# ETHERNET_PHY.net
KiCad netlist of a schematic drawn in Altium Designer
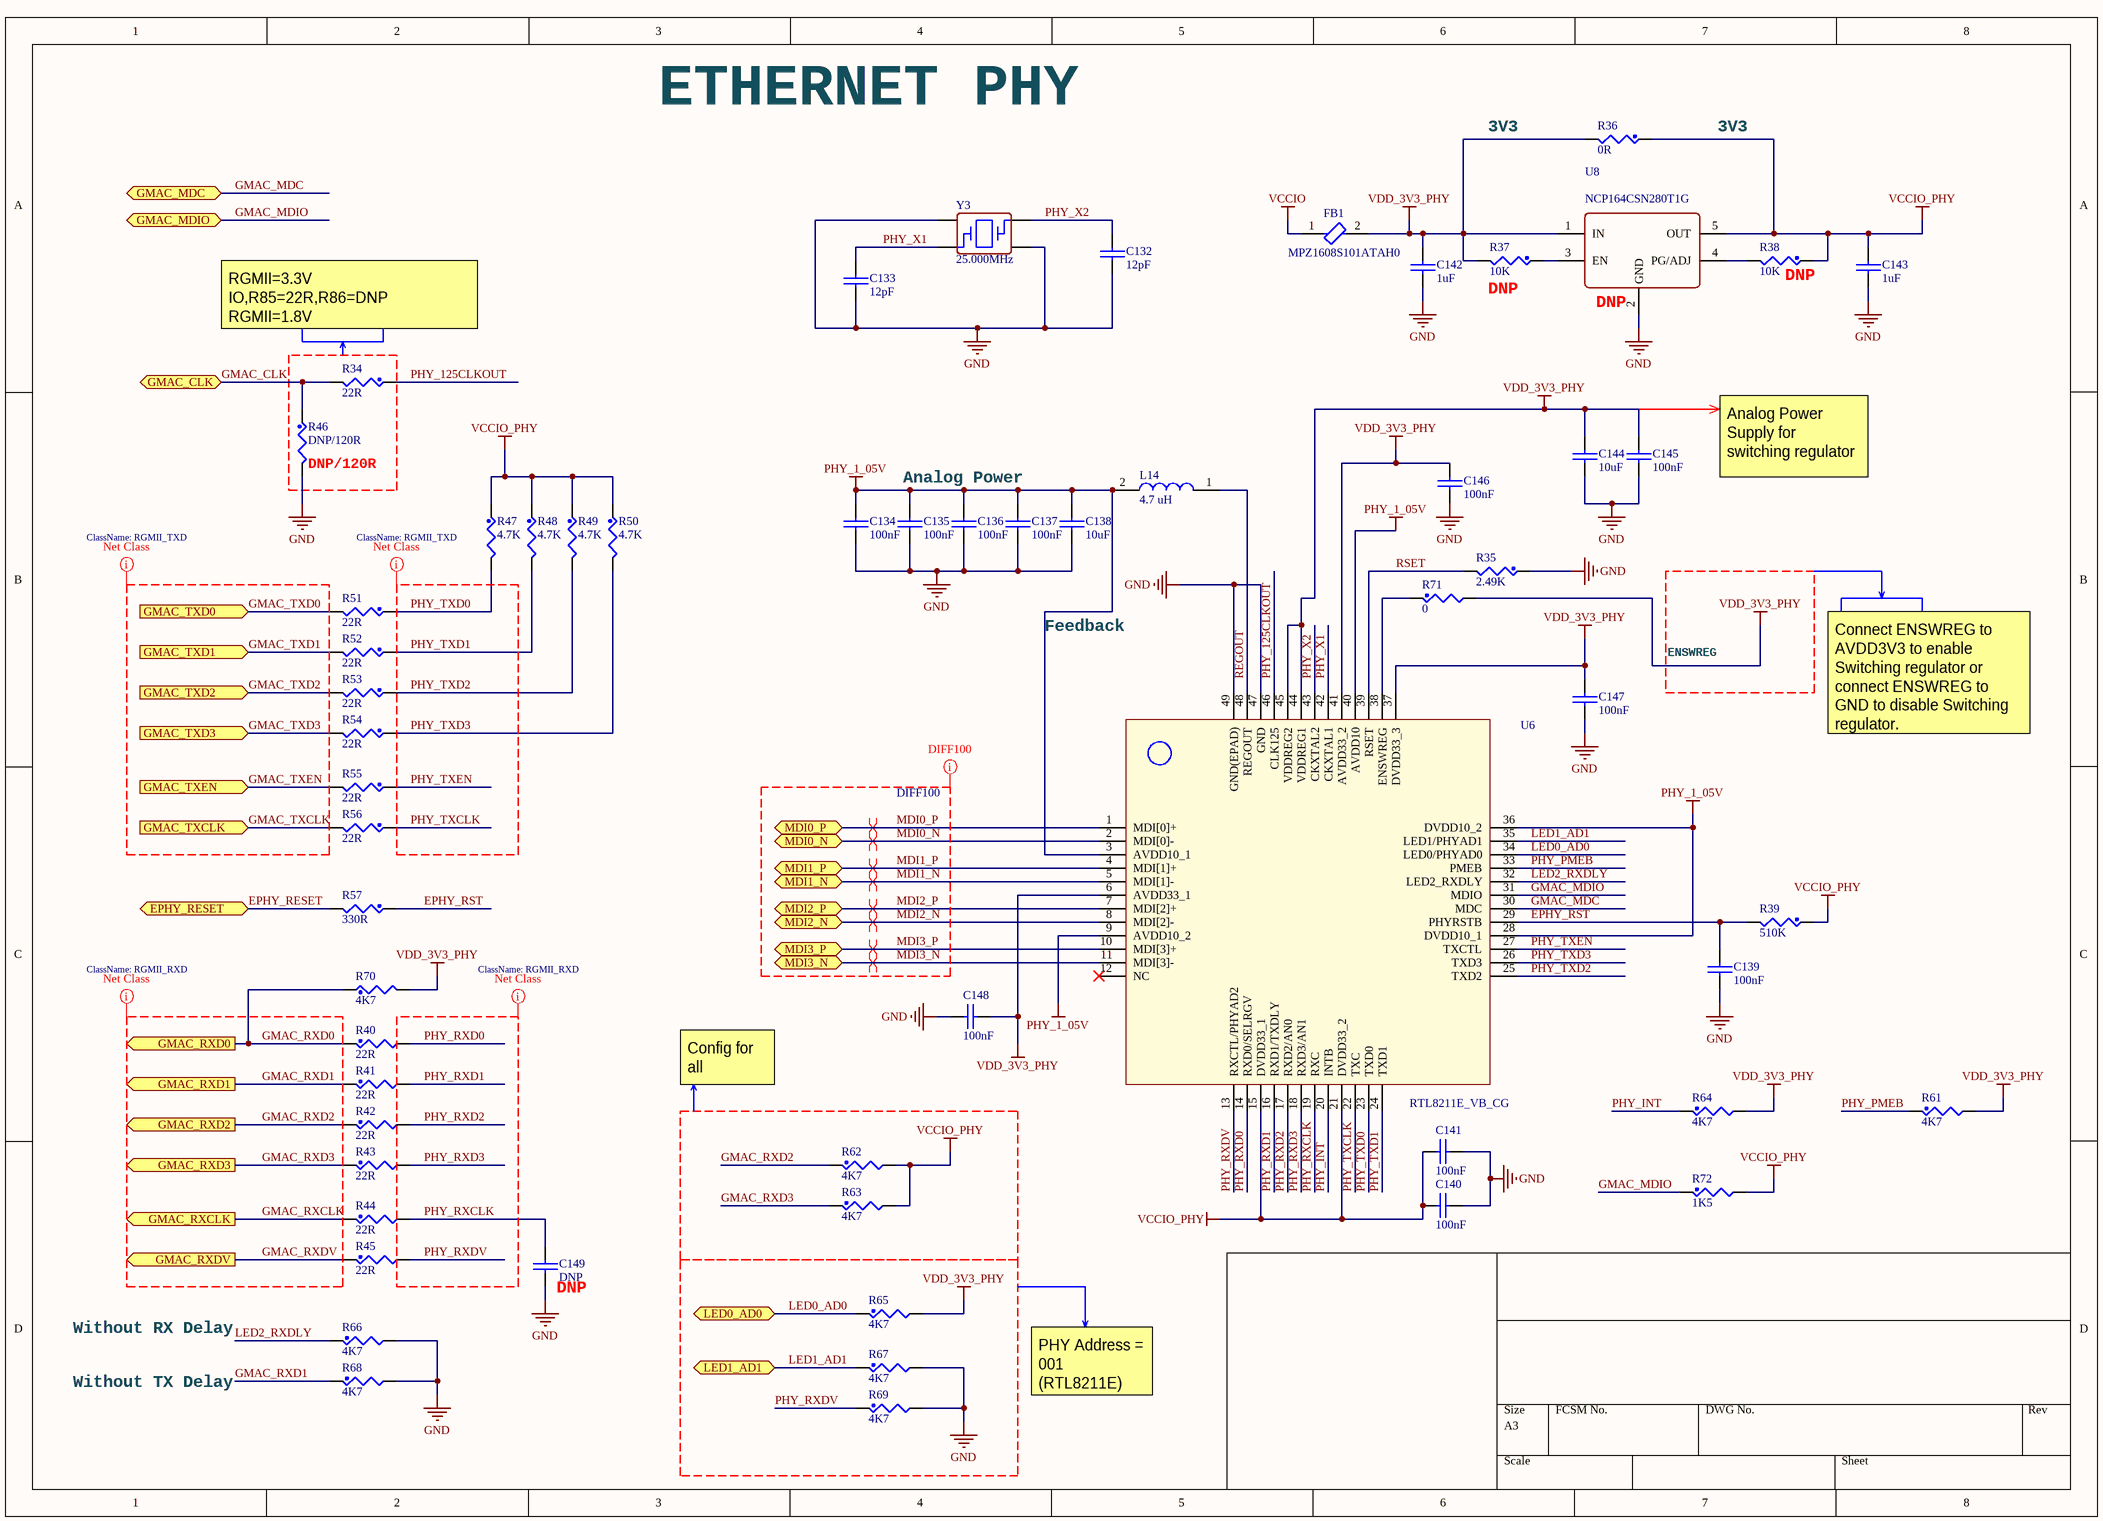
[diagram p0: ETHERNET_PHY.SchDoc]

(export (version "E")
  (design (tool "Eeschema 10.0.6"))
  (components
    (comp (ref "C132")
      (value "12pF")
      (footprint "0402_CC - C")
      (libsource (lib "AAR_RockChip_RK3328") (part "CAP_NP"))
    )
    (comp (ref "C133")
      (value "12pF")
      (footprint "0402_CC - C")
      (libsource (lib "AAR_RockChip_RK3328") (part "CAP_NP"))
    )
    (comp (ref "C134")
      (value "100nF")
      (footprint "0402_CC - C")
      (libsource (lib "AAR_RockChip_RK3328") (part "CAP_NP"))
    )
    (comp (ref "C135")
      (value "100nF")
      (footprint "0402_CC - C")
      (libsource (lib "AAR_RockChip_RK3328") (part "CAP_NP"))
    )
    (comp (ref "C136")
      (value "100nF")
      (footprint "0402_CC - C")
      (libsource (lib "AAR_RockChip_RK3328") (part "CAP_NP"))
    )
    (comp (ref "C137")
      (value "100nF")
      (footprint "0402_CC - C")
      (libsource (lib "AAR_RockChip_RK3328") (part "CAP_NP"))
    )
    (comp (ref "C138")
      (value "10uF")
      (footprint "0603_CC")
      (libsource (lib "AAR_RockChip_RK3328") (part "CAP_NP"))
    )
    (comp (ref "C139")
      (value "100nF")
      (footprint "0402_CC - C")
      (libsource (lib "AAR_RockChip_RK3328") (part "CAP_NP"))
    )
    (comp (ref "C140")
      (value "100nF")
      (footprint "0402_CC - C")
      (libsource (lib "AAR_RockChip_RK3328") (part "CAP_NP"))
    )
    (comp (ref "C141")
      (value "100nF")
      (footprint "0402_CC - C")
      (libsource (lib "AAR_RockChip_RK3328") (part "CAP_NP"))
    )
    (comp (ref "C142")
      (value "1uF")
      (footprint "0402_CC - C")
      (libsource (lib "AAR_RockChip_RK3328") (part "CAP_NP"))
    )
    (comp (ref "C143")
      (value "1uF")
      (footprint "0402_CC - C")
      (libsource (lib "AAR_RockChip_RK3328") (part "CAP_NP"))
    )
    (comp (ref "C144")
      (value "10uF")
      (footprint "0603_CC")
      (libsource (lib "AAR_RockChip_RK3328") (part "CAP_NP"))
    )
    (comp (ref "C145")
      (value "100nF")
      (footprint "0402_CC - C")
      (libsource (lib "AAR_RockChip_RK3328") (part "CAP_NP"))
    )
    (comp (ref "C146")
      (value "100nF")
      (footprint "0402_CC - C")
      (libsource (lib "AAR_RockChip_RK3328") (part "CAP_NP"))
    )
    (comp (ref "C147")
      (value "100nF")
      (footprint "0402_CC - C")
      (libsource (lib "AAR_RockChip_RK3328") (part "CAP_NP"))
    )
    (comp (ref "C148")
      (value "100nF")
      (footprint "0402_CC - C")
      (libsource (lib "AAR_RockChip_RK3328") (part "CAP_NP"))
    )
    (comp (ref "C149")
      (value "DNP")
      (footprint "0402_CC - C")
      (libsource (lib "AAR_RockChip_RK3328") (part "CAP_NP"))
    )
    (comp (ref "FB1")
      (value "MPZ1608S101ATAH0")
      (footprint "FP-MPZ1608-0_6-IPC_A")
      (description "Ferrite Beads 100ohms 3A 30mOhms 0603 Ferrite Chip\r\nCreator ARMAN")
      (fields (field (name "TOLERANCE") "25%") (field (name "MFR") "TDK"))
      (libsource (lib "AAR_RockChip_RK3328") (part "MPZ1608S101ATAH0"))
    )
    (comp (ref "L14")
      (value "4.7 uH")
      (footprint "1285ASH1R0MP2")
      (description "Fixed Inductors 08064.7 uH 20% 4.8A RDC=0.032ohms\r\nCreator Arman")
      (fields (field (name "MFR") "Murata Electronics") (field (name "MFR_PART_NO") "DFE201610E-4R7M=P2"))
      (libsource (lib "AAR_RockChip_RK3328") (part "DFE201610E_4R7M_P2_1"))
    )
    (comp (ref "R34")
      (value "22R")
      (footprint "0402_CR")
      (libsource (lib "AAR_RockChip_RK3328") (part "RES"))
    )
    (comp (ref "R35")
      (value "2.49K")
      (footprint "0402_CR")
      (libsource (lib "AAR_RockChip_RK3328") (part "RES"))
    )
    (comp (ref "R36") (value "0R") (footprint "0402_CR") (libsource (lib "AAR_RockChip_RK3328") (part "RES")))
    (comp (ref "R37")
      (value "10K")
      (footprint "0402_CR")
      (libsource (lib "AAR_RockChip_RK3328") (part "RES"))
    )
    (comp (ref "R38")
      (value "10K")
      (footprint "0402_CR")
      (libsource (lib "AAR_RockChip_RK3328") (part "RES"))
    )
    (comp (ref "R39")
      (value "510K")
      (footprint "0402_CR")
      (libsource (lib "AAR_RockChip_RK3328") (part "RES"))
    )
    (comp (ref "R40")
      (value "22R")
      (footprint "0402_CR")
      (libsource (lib "AAR_RockChip_RK3328") (part "RES"))
    )
    (comp (ref "R41")
      (value "22R")
      (footprint "0402_CR")
      (libsource (lib "AAR_RockChip_RK3328") (part "RES"))
    )
    (comp (ref "R42")
      (value "22R")
      (footprint "0402_CR")
      (libsource (lib "AAR_RockChip_RK3328") (part "RES"))
    )
    (comp (ref "R43")
      (value "22R")
      (footprint "0402_CR")
      (libsource (lib "AAR_RockChip_RK3328") (part "RES"))
    )
    (comp (ref "R44")
      (value "22R")
      (footprint "0402_CR")
      (libsource (lib "AAR_RockChip_RK3328") (part "RES"))
    )
    (comp (ref "R45")
      (value "22R")
      (footprint "0402_CR")
      (libsource (lib "AAR_RockChip_RK3328") (part "RES"))
    )
    (comp (ref "R46")
      (value "DNP/120R")
      (footprint "0402_CR")
      (libsource (lib "AAR_RockChip_RK3328") (part "RES"))
    )
    (comp (ref "R47")
      (value "4.7K")
      (footprint "0402_CR")
      (libsource (lib "AAR_RockChip_RK3328") (part "RES"))
    )
    (comp (ref "R48")
      (value "4.7K")
      (footprint "0402_CR")
      (libsource (lib "AAR_RockChip_RK3328") (part "RES"))
    )
    (comp (ref "R49")
      (value "4.7K")
      (footprint "0402_CR")
      (libsource (lib "AAR_RockChip_RK3328") (part "RES"))
    )
    (comp (ref "R50")
      (value "4.7K")
      (footprint "0402_CR")
      (libsource (lib "AAR_RockChip_RK3328") (part "RES"))
    )
    (comp (ref "R51")
      (value "22R")
      (footprint "0402_CR")
      (libsource (lib "AAR_RockChip_RK3328") (part "RES"))
    )
    (comp (ref "R52")
      (value "22R")
      (footprint "0402_CR")
      (libsource (lib "AAR_RockChip_RK3328") (part "RES"))
    )
    (comp (ref "R53")
      (value "22R")
      (footprint "0402_CR")
      (libsource (lib "AAR_RockChip_RK3328") (part "RES"))
    )
    (comp (ref "R54")
      (value "22R")
      (footprint "0402_CR")
      (libsource (lib "AAR_RockChip_RK3328") (part "RES"))
    )
    (comp (ref "R55")
      (value "22R")
      (footprint "0402_CR")
      (libsource (lib "AAR_RockChip_RK3328") (part "RES"))
    )
    (comp (ref "R56")
      (value "22R")
      (footprint "0402_CR")
      (libsource (lib "AAR_RockChip_RK3328") (part "RES"))
    )
    (comp (ref "R57")
      (value "330R")
      (footprint "0402_CR")
      (libsource (lib "AAR_RockChip_RK3328") (part "RES"))
    )
    (comp (ref "R61")
      (value "4K7")
      (footprint "0402_CR")
      (libsource (lib "AAR_RockChip_RK3328") (part "RES"))
    )
    (comp (ref "R62")
      (value "4K7")
      (footprint "0402_CR")
      (libsource (lib "AAR_RockChip_RK3328") (part "RES"))
    )
    (comp (ref "R63")
      (value "4K7")
      (footprint "0402_CR")
      (libsource (lib "AAR_RockChip_RK3328") (part "RES"))
    )
    (comp (ref "R64")
      (value "4K7")
      (footprint "0402_CR")
      (libsource (lib "AAR_RockChip_RK3328") (part "RES"))
    )
    (comp (ref "R65")
      (value "4K7")
      (footprint "0402_CR")
      (libsource (lib "AAR_RockChip_RK3328") (part "RES"))
    )
    (comp (ref "R66")
      (value "4K7")
      (footprint "0402_CR")
      (libsource (lib "AAR_RockChip_RK3328") (part "RES"))
    )
    (comp (ref "R67")
      (value "4K7")
      (footprint "0402_CR")
      (libsource (lib "AAR_RockChip_RK3328") (part "RES"))
    )
    (comp (ref "R68")
      (value "4K7")
      (footprint "0402_CR")
      (libsource (lib "AAR_RockChip_RK3328") (part "RES"))
    )
    (comp (ref "R69")
      (value "4K7")
      (footprint "0402_CR")
      (libsource (lib "AAR_RockChip_RK3328") (part "RES"))
    )
    (comp (ref "R70")
      (value "4K7")
      (footprint "0402_CR")
      (libsource (lib "AAR_RockChip_RK3328") (part "RES"))
    )
    (comp (ref "R71") (value "0") (footprint "0402_CR") (libsource (lib "AAR_RockChip_RK3328") (part "RES")))
    (comp (ref "R72")
      (value "1K5")
      (footprint "0402_CR")
      (libsource (lib "AAR_RockChip_RK3328") (part "RES"))
    )
    (comp (ref "U6")
      (value "RTL8211E_VB_CG")
      (footprint "QFN40P600X600X100-49N")
      (fields (field (name "MFR_PART_NO") "RTL8211E-VB-CG") (field (name "LCSC PART #") "C90735"))
      (libsource (lib "AAR_RockChip_RK3328") (part "RTL8211E_VB_CG"))
    )
    (comp (ref "U8")
      (value "NCP164CSN280T1G")
      (footprint "TSOP-5")
      (description "LDO Regulator, 300mA,\r\nLow Dropout Voltage, Ultra\r\nLow Noise, High PSRR with\r\nPower Good")
      (fields (field (name "MFR") "ON Semiconductor"))
      (libsource (lib "AAR_RockChip_RK3328") (part "NCP164CSN280T1G"))
    )
    (comp (ref "Y3")
      (value "25.000MHz")
      (footprint "ABM8G")
      (description "CRYSTAL 25MHZ 18PF SMD\r\nCreated by Arman Arvand")
      (fields
        (field (name "MFR") "Abracon Corporation")
        (field (name "MFR_PART_NO") "ABM8G-25.000MHZ-18-D2Y-T")
      )
      (libsource (lib "AAR_RockChip_RK3328") (part "ABM8G-25.000MHZ-18-D2Y-T"))
    )
  )
  (nets
    (net (code "1") (name "/EPHY_RESET") (class "Default")
      (node (ref "R57") (pin "2") (pinfunction "2_2") (pintype "passive"))
    )
    (net (code "2") (name "/EPHY_RST") (class "Default")
      (node (ref "C139") (pin "1") (pinfunction "1_1") (pintype "passive"))
      (node (ref "R39") (pin "2") (pinfunction "2_2") (pintype "passive"))
      (node (ref "R57") (pin "1") (pinfunction "1_1") (pintype "passive"))
      (node (ref "U6") (pin "29") (pinfunction "PHYRSTB_29") (pintype "passive"))
    )
    (net (code "3") (name "/GMAC_CLK") (class "Default")
      (node (ref "R34") (pin "2") (pinfunction "2_2") (pintype "passive"))
      (node (ref "R46") (pin "1") (pinfunction "1_1") (pintype "passive"))
    )
    (net (code "4") (name "/GMAC_MDC") (class "Default")
      (node (ref "U6") (pin "30") (pinfunction "MDC_30") (pintype "passive"))
    )
    (net (code "5") (name "/GMAC_MDIO") (class "Default")
      (node (ref "R72") (pin "1") (pinfunction "1_1") (pintype "passive"))
      (node (ref "U6") (pin "31") (pinfunction "MDIO_31") (pintype "passive"))
    )
    (net (code "6") (name "/GMAC_RXCLK") (class "Default")
      (node (ref "R44") (pin "1") (pinfunction "1_1") (pintype "passive"))
    )
    (net (code "7") (name "/GMAC_RXD0") (class "Default")
      (node (ref "R40") (pin "1") (pinfunction "1_1") (pintype "passive"))
      (node (ref "R70") (pin "1") (pinfunction "1_1") (pintype "passive"))
    )
    (net (code "8") (name "/GMAC_RXD1") (class "Default")
      (node (ref "R41") (pin "1") (pinfunction "1_1") (pintype "passive"))
      (node (ref "R68") (pin "1") (pinfunction "1_1") (pintype "passive"))
    )
    (net (code "9") (name "/GMAC_RXD2") (class "Default")
      (node (ref "R42") (pin "1") (pinfunction "1_1") (pintype "passive"))
      (node (ref "R62") (pin "1") (pinfunction "1_1") (pintype "passive"))
    )
    (net (code "10") (name "/GMAC_RXD3") (class "Default")
      (node (ref "R43") (pin "1") (pinfunction "1_1") (pintype "passive"))
      (node (ref "R63") (pin "1") (pinfunction "1_1") (pintype "passive"))
    )
    (net (code "11") (name "/GMAC_RXDV") (class "Default")
      (node (ref "R45") (pin "1") (pinfunction "1_1") (pintype "passive"))
    )
    (net (code "12") (name "/GMAC_TXCLK") (class "Default")
      (node (ref "R56") (pin "2") (pinfunction "2_2") (pintype "passive"))
    )
    (net (code "13") (name "/GMAC_TXD0") (class "Default")
      (node (ref "R51") (pin "2") (pinfunction "2_2") (pintype "passive"))
    )
    (net (code "14") (name "/GMAC_TXD1") (class "Default")
      (node (ref "R52") (pin "2") (pinfunction "2_2") (pintype "passive"))
    )
    (net (code "15") (name "/GMAC_TXD2") (class "Default")
      (node (ref "R53") (pin "2") (pinfunction "2_2") (pintype "passive"))
    )
    (net (code "16") (name "/GMAC_TXD3") (class "Default")
      (node (ref "R54") (pin "2") (pinfunction "2_2") (pintype "passive"))
    )
    (net (code "17") (name "/GMAC_TXEN") (class "Default")
      (node (ref "R55") (pin "2") (pinfunction "2_2") (pintype "passive"))
    )
    (net (code "18") (name "/LED0_AD0") (class "Default")
      (node (ref "R65") (pin "1") (pinfunction "1_1") (pintype "passive"))
      (node (ref "U6") (pin "34") (pinfunction "LED0/PHYAD0_34") (pintype "passive"))
    )
    (net (code "19") (name "/LED1_AD1") (class "Default")
      (node (ref "R67") (pin "1") (pinfunction "1_1") (pintype "passive"))
      (node (ref "U6") (pin "35") (pinfunction "LED1/PHYAD1_35") (pintype "passive"))
    )
    (net (code "20") (name "/LED2_RXDLY") (class "Default")
      (node (ref "R66") (pin "1") (pinfunction "1_1") (pintype "passive"))
      (node (ref "U6") (pin "32") (pinfunction "LED2_RXDLY_32") (pintype "passive"))
    )
    (net (code "21") (name "/MDI0_N") (class "Default")
      (node (ref "U6") (pin "2") (pinfunction "MDI[0]-_2") (pintype "passive"))
    )
    (net (code "22") (name "/MDI0_P") (class "Default")
      (node (ref "U6") (pin "1") (pinfunction "MDI[0]+_1") (pintype "passive"))
    )
    (net (code "23") (name "/MDI1_N") (class "Default")
      (node (ref "U6") (pin "5") (pinfunction "MDI[1]-_5") (pintype "passive"))
    )
    (net (code "24") (name "/MDI1_P") (class "Default")
      (node (ref "U6") (pin "4") (pinfunction "MDI[1]+_4") (pintype "passive"))
    )
    (net (code "25") (name "/MDI2_N") (class "Default")
      (node (ref "U6") (pin "8") (pinfunction "MDI[2]-_8") (pintype "passive"))
    )
    (net (code "26") (name "/MDI2_P") (class "Default")
      (node (ref "U6") (pin "7") (pinfunction "MDI[2]+_7") (pintype "passive"))
    )
    (net (code "27") (name "/MDI3_N") (class "Default")
      (node (ref "U6") (pin "11") (pinfunction "MDI[3]-_11") (pintype "passive"))
    )
    (net (code "28") (name "/MDI3_P") (class "Default")
      (node (ref "U6") (pin "10") (pinfunction "MDI[3]+_10") (pintype "passive"))
    )
    (net (code "29") (name "/PHY_125CLKOUT") (class "Default")
      (node (ref "R34") (pin "1") (pinfunction "1_1") (pintype "passive"))
      (node (ref "U6") (pin "46") (pinfunction "CLK125_46") (pintype "passive"))
    )
    (net (code "30") (name "/PHY_INT") (class "Default")
      (node (ref "R64") (pin "1") (pinfunction "1_1") (pintype "passive"))
      (node (ref "U6") (pin "20") (pinfunction "INTB_20") (pintype "passive"))
    )
    (net (code "31") (name "/PHY_PMEB") (class "Default")
      (node (ref "R61") (pin "1") (pinfunction "1_1") (pintype "passive"))
      (node (ref "U6") (pin "33") (pinfunction "PMEB_33") (pintype "passive"))
    )
    (net (code "32") (name "/PHY_RXCLK") (class "Default")
      (node (ref "C149") (pin "2") (pinfunction "2_2") (pintype "passive"))
      (node (ref "R44") (pin "2") (pinfunction "2_2") (pintype "passive"))
      (node (ref "U6") (pin "19") (pinfunction "RXC_19") (pintype "passive"))
    )
    (net (code "33") (name "/PHY_RXD0") (class "Default")
      (node (ref "R40") (pin "2") (pinfunction "2_2") (pintype "passive"))
      (node (ref "U6") (pin "14") (pinfunction "RXD0/SELRGV_14") (pintype "passive"))
    )
    (net (code "34") (name "/PHY_RXD1") (class "Default")
      (node (ref "R41") (pin "2") (pinfunction "2_2") (pintype "passive"))
      (node (ref "U6") (pin "16") (pinfunction "RXD1/TXDLY_16") (pintype "passive"))
    )
    (net (code "35") (name "/PHY_RXD2") (class "Default")
      (node (ref "R42") (pin "2") (pinfunction "2_2") (pintype "passive"))
      (node (ref "U6") (pin "17") (pinfunction "RXD2/AN0_17") (pintype "passive"))
    )
    (net (code "36") (name "/PHY_RXD3") (class "Default")
      (node (ref "R43") (pin "2") (pinfunction "2_2") (pintype "passive"))
      (node (ref "U6") (pin "18") (pinfunction "RXD3/AN1_18") (pintype "passive"))
    )
    (net (code "37") (name "/PHY_RXDV") (class "Default")
      (node (ref "R45") (pin "2") (pinfunction "2_2") (pintype "passive"))
      (node (ref "R69") (pin "1") (pinfunction "1_1") (pintype "passive"))
      (node (ref "U6") (pin "13") (pinfunction "RXCTL/PHYAD2_13") (pintype "passive"))
    )
    (net (code "38") (name "/PHY_TXCLK") (class "Default")
      (node (ref "R56") (pin "1") (pinfunction "1_1") (pintype "passive"))
      (node (ref "U6") (pin "22") (pinfunction "TXC_22") (pintype "passive"))
    )
    (net (code "39") (name "/PHY_TXD0") (class "Default")
      (node (ref "R47") (pin "2") (pinfunction "2_2") (pintype "passive"))
      (node (ref "R51") (pin "1") (pinfunction "1_1") (pintype "passive"))
      (node (ref "U6") (pin "23") (pinfunction "TXD0_23") (pintype "passive"))
    )
    (net (code "40") (name "/PHY_TXD1") (class "Default")
      (node (ref "R48") (pin "2") (pinfunction "2_2") (pintype "passive"))
      (node (ref "R52") (pin "1") (pinfunction "1_1") (pintype "passive"))
      (node (ref "U6") (pin "24") (pinfunction "TXD1_24") (pintype "passive"))
    )
    (net (code "41") (name "/PHY_TXD2") (class "Default")
      (node (ref "R49") (pin "2") (pinfunction "2_2") (pintype "passive"))
      (node (ref "R53") (pin "1") (pinfunction "1_1") (pintype "passive"))
      (node (ref "U6") (pin "25") (pinfunction "TXD2_25") (pintype "passive"))
    )
    (net (code "42") (name "/PHY_TXD3") (class "Default")
      (node (ref "R50") (pin "2") (pinfunction "2_2") (pintype "passive"))
      (node (ref "R54") (pin "1") (pinfunction "1_1") (pintype "passive"))
      (node (ref "U6") (pin "26") (pinfunction "TXD3_26") (pintype "passive"))
    )
    (net (code "43") (name "/PHY_TXEN") (class "Default")
      (node (ref "R55") (pin "1") (pinfunction "1_1") (pintype "passive"))
      (node (ref "U6") (pin "27") (pinfunction "TXCTL_27") (pintype "passive"))
    )
    (net (code "44") (name "/PHY_X1") (class "Default")
      (node (ref "C133") (pin "1") (pinfunction "1_1") (pintype "passive"))
      (node (ref "U6") (pin "42") (pinfunction "CKXTAL1_42") (pintype "passive"))
      (node (ref "Y3") (pin "1") (pinfunction "1_1") (pintype "passive"))
    )
    (net (code "45") (name "/PHY_X2") (class "Default")
      (node (ref "C132") (pin "1") (pinfunction "1_1") (pintype "passive"))
      (node (ref "U6") (pin "43") (pinfunction "CKXTAL2_43") (pintype "passive"))
      (node (ref "Y3") (pin "3") (pinfunction "3_3") (pintype "passive"))
    )
    (net (code "46") (name "/REGOUT") (class "Default")
      (node (ref "L14") (pin "1") (pinfunction "1_1") (pintype "passive"))
      (node (ref "U6") (pin "48") (pinfunction "REGOUT_48") (pintype "passive"))
    )
    (net (code "47") (name "/RSET") (class "Default")
      (node (ref "R35") (pin "2") (pinfunction "2_2") (pintype "passive"))
      (node (ref "U6") (pin "39") (pinfunction "RSET_39") (pintype "passive"))
    )
    (net (code "48") (name "GND") (class "Default")
      (node (ref "C132") (pin "2") (pinfunction "2_2") (pintype "passive"))
      (node (ref "C133") (pin "2") (pinfunction "2_2") (pintype "passive"))
      (node (ref "C134") (pin "2") (pinfunction "2_2") (pintype "passive"))
      (node (ref "C135") (pin "2") (pinfunction "2_2") (pintype "passive"))
      (node (ref "C136") (pin "2") (pinfunction "2_2") (pintype "passive"))
      (node (ref "C137") (pin "2") (pinfunction "2_2") (pintype "passive"))
      (node (ref "C138") (pin "2") (pinfunction "2_2") (pintype "passive"))
      (node (ref "C139") (pin "2") (pinfunction "2_2") (pintype "passive"))
      (node (ref "C140") (pin "2") (pinfunction "2_2") (pintype "passive"))
      (node (ref "C141") (pin "2") (pinfunction "2_2") (pintype "passive"))
      (node (ref "C142") (pin "2") (pinfunction "2_2") (pintype "passive"))
      (node (ref "C143") (pin "2") (pinfunction "2_2") (pintype "passive"))
      (node (ref "C144") (pin "2") (pinfunction "2_2") (pintype "passive"))
      (node (ref "C145") (pin "2") (pinfunction "2_2") (pintype "passive"))
      (node (ref "C146") (pin "1") (pinfunction "1_1") (pintype "passive"))
      (node (ref "C147") (pin "1") (pinfunction "1_1") (pintype "passive"))
      (node (ref "C148") (pin "1") (pinfunction "1_1") (pintype "passive"))
      (node (ref "C149") (pin "1") (pinfunction "1_1") (pintype "passive"))
      (node (ref "R35") (pin "1") (pinfunction "1_1") (pintype "passive"))
      (node (ref "R46") (pin "2") (pinfunction "2_2") (pintype "passive"))
      (node (ref "R66") (pin "2") (pinfunction "2_2") (pintype "passive"))
      (node (ref "R67") (pin "2") (pinfunction "2_2") (pintype "passive"))
      (node (ref "R68") (pin "2") (pinfunction "2_2") (pintype "passive"))
      (node (ref "R69") (pin "2") (pinfunction "2_2") (pintype "passive"))
      (node (ref "U6") (pin "47") (pinfunction "GND_47") (pintype "power_in"))
      (node (ref "U6") (pin "49") (pinfunction "GND(EPAD)_49") (pintype "passive"))
      (node (ref "U8") (pin "2") (pinfunction "GND_2") (pintype "passive"))
      (node (ref "Y3") (pin "2") (pinfunction "2_2") (pintype "passive"))
      (node (ref "Y3") (pin "4") (pinfunction "4_4") (pintype "passive"))
    )
    (net (code "49") (name "Net-(U6-ENSWREG)") (class "Default")
      (node (ref "R71") (pin "1") (pinfunction "1_1") (pintype "passive"))
      (node (ref "U6") (pin "38") (pinfunction "ENSWREG_38") (pintype "passive"))
    )
    (net (code "50") (name "Net-(U8-EN)") (class "Default")
      (node (ref "R37") (pin "1") (pinfunction "1_1") (pintype "passive"))
      (node (ref "U8") (pin "3") (pinfunction "EN_3") (pintype "passive"))
    )
    (net (code "51") (name "Net-(U8-PG{slash}ADJ)") (class "Default")
      (node (ref "R38") (pin "2") (pinfunction "2_2") (pintype "passive"))
      (node (ref "U8") (pin "4") (pinfunction "PG/ADJ_4") (pintype "passive"))
    )
    (net (code "52") (name "PHY_1_05V") (class "Default")
      (node (ref "C134") (pin "1") (pinfunction "1_1") (pintype "passive"))
      (node (ref "C135") (pin "1") (pinfunction "1_1") (pintype "passive"))
      (node (ref "C136") (pin "1") (pinfunction "1_1") (pintype "passive"))
      (node (ref "C137") (pin "1") (pinfunction "1_1") (pintype "passive"))
      (node (ref "C138") (pin "1") (pinfunction "1_1") (pintype "passive"))
      (node (ref "L14") (pin "2") (pinfunction "2_2") (pintype "passive"))
      (node (ref "U6") (pin "28") (pinfunction "DVDD10_1_28") (pintype "passive"))
      (node (ref "U6") (pin "3") (pinfunction "AVDD10_1_3") (pintype "passive"))
      (node (ref "U6") (pin "36") (pinfunction "DVDD10_2_36") (pintype "passive"))
      (node (ref "U6") (pin "40") (pinfunction "AVDD10_40") (pintype "power_in"))
      (node (ref "U6") (pin "9") (pinfunction "AVDD10_2_9") (pintype "power_in"))
    )
    (net (code "53") (name "VCCIO") (class "Default")
      (node (ref "FB1") (pin "1") (pinfunction "1_1") (pintype "passive"))
    )
    (net (code "54") (name "VCCIO_PHY") (class "Default")
      (node (ref "C140") (pin "1") (pinfunction "1_1") (pintype "passive"))
      (node (ref "C141") (pin "1") (pinfunction "1_1") (pintype "passive"))
      (node (ref "C143") (pin "1") (pinfunction "1_1") (pintype "passive"))
      (node (ref "R36") (pin "1") (pinfunction "1_1") (pintype "passive"))
      (node (ref "R38") (pin "1") (pinfunction "1_1") (pintype "passive"))
      (node (ref "R39") (pin "1") (pinfunction "1_1") (pintype "passive"))
      (node (ref "R47") (pin "1") (pinfunction "1_1") (pintype "passive"))
      (node (ref "R48") (pin "1") (pinfunction "1_1") (pintype "passive"))
      (node (ref "R49") (pin "1") (pinfunction "1_1") (pintype "passive"))
      (node (ref "R50") (pin "1") (pinfunction "1_1") (pintype "passive"))
      (node (ref "R62") (pin "2") (pinfunction "2_2") (pintype "passive"))
      (node (ref "R63") (pin "2") (pinfunction "2_2") (pintype "passive"))
      (node (ref "R72") (pin "2") (pinfunction "2_2") (pintype "passive"))
      (node (ref "U6") (pin "15") (pinfunction "DVDD33_1_15") (pintype "power_in"))
      (node (ref "U6") (pin "21") (pinfunction "DVDD33_2_21") (pintype "power_in"))
      (node (ref "U8") (pin "5") (pinfunction "OUT_5") (pintype "passive"))
    )
    (net (code "55") (name "VDD_3V3_PHY") (class "Default")
      (node (ref "C142") (pin "1") (pinfunction "1_1") (pintype "passive"))
      (node (ref "C144") (pin "1") (pinfunction "1_1") (pintype "passive"))
      (node (ref "C145") (pin "1") (pinfunction "1_1") (pintype "passive"))
      (node (ref "C146") (pin "2") (pinfunction "2_2") (pintype "passive"))
      (node (ref "C147") (pin "2") (pinfunction "2_2") (pintype "passive"))
      (node (ref "C148") (pin "2") (pinfunction "2_2") (pintype "passive"))
      (node (ref "FB1") (pin "2") (pinfunction "2_2") (pintype "passive"))
      (node (ref "R36") (pin "2") (pinfunction "2_2") (pintype "passive"))
      (node (ref "R37") (pin "2") (pinfunction "2_2") (pintype "passive"))
      (node (ref "R61") (pin "2") (pinfunction "2_2") (pintype "passive"))
      (node (ref "R64") (pin "2") (pinfunction "2_2") (pintype "passive"))
      (node (ref "R65") (pin "2") (pinfunction "2_2") (pintype "passive"))
      (node (ref "R70") (pin "2") (pinfunction "2_2") (pintype "passive"))
      (node (ref "R71") (pin "2") (pinfunction "2_2") (pintype "passive"))
      (node (ref "U6") (pin "37") (pinfunction "DVDD33_3_37") (pintype "power_in"))
      (node (ref "U6") (pin "41") (pinfunction "AVDD33_2_41") (pintype "power_in"))
      (node (ref "U6") (pin "44") (pinfunction "VDDREG1_44") (pintype "power_in"))
      (node (ref "U6") (pin "45") (pinfunction "VDDREG2_45") (pintype "power_in"))
      (node (ref "U6") (pin "6") (pinfunction "AVDD33_1_6") (pintype "power_in"))
      (node (ref "U8") (pin "1") (pinfunction "IN_1") (pintype "passive"))
    )
    (net (code "56") (name "unconnected-(U6-NC-Pad12)") (class "Default")
      (node (ref "U6") (pin "12") (pinfunction "NC_12") (pintype "passive+no_connect"))
    )
  )
)
